# LPCB228_-_POWERUP.net
KiCad netlist of a schematic drawn in Altium Designer
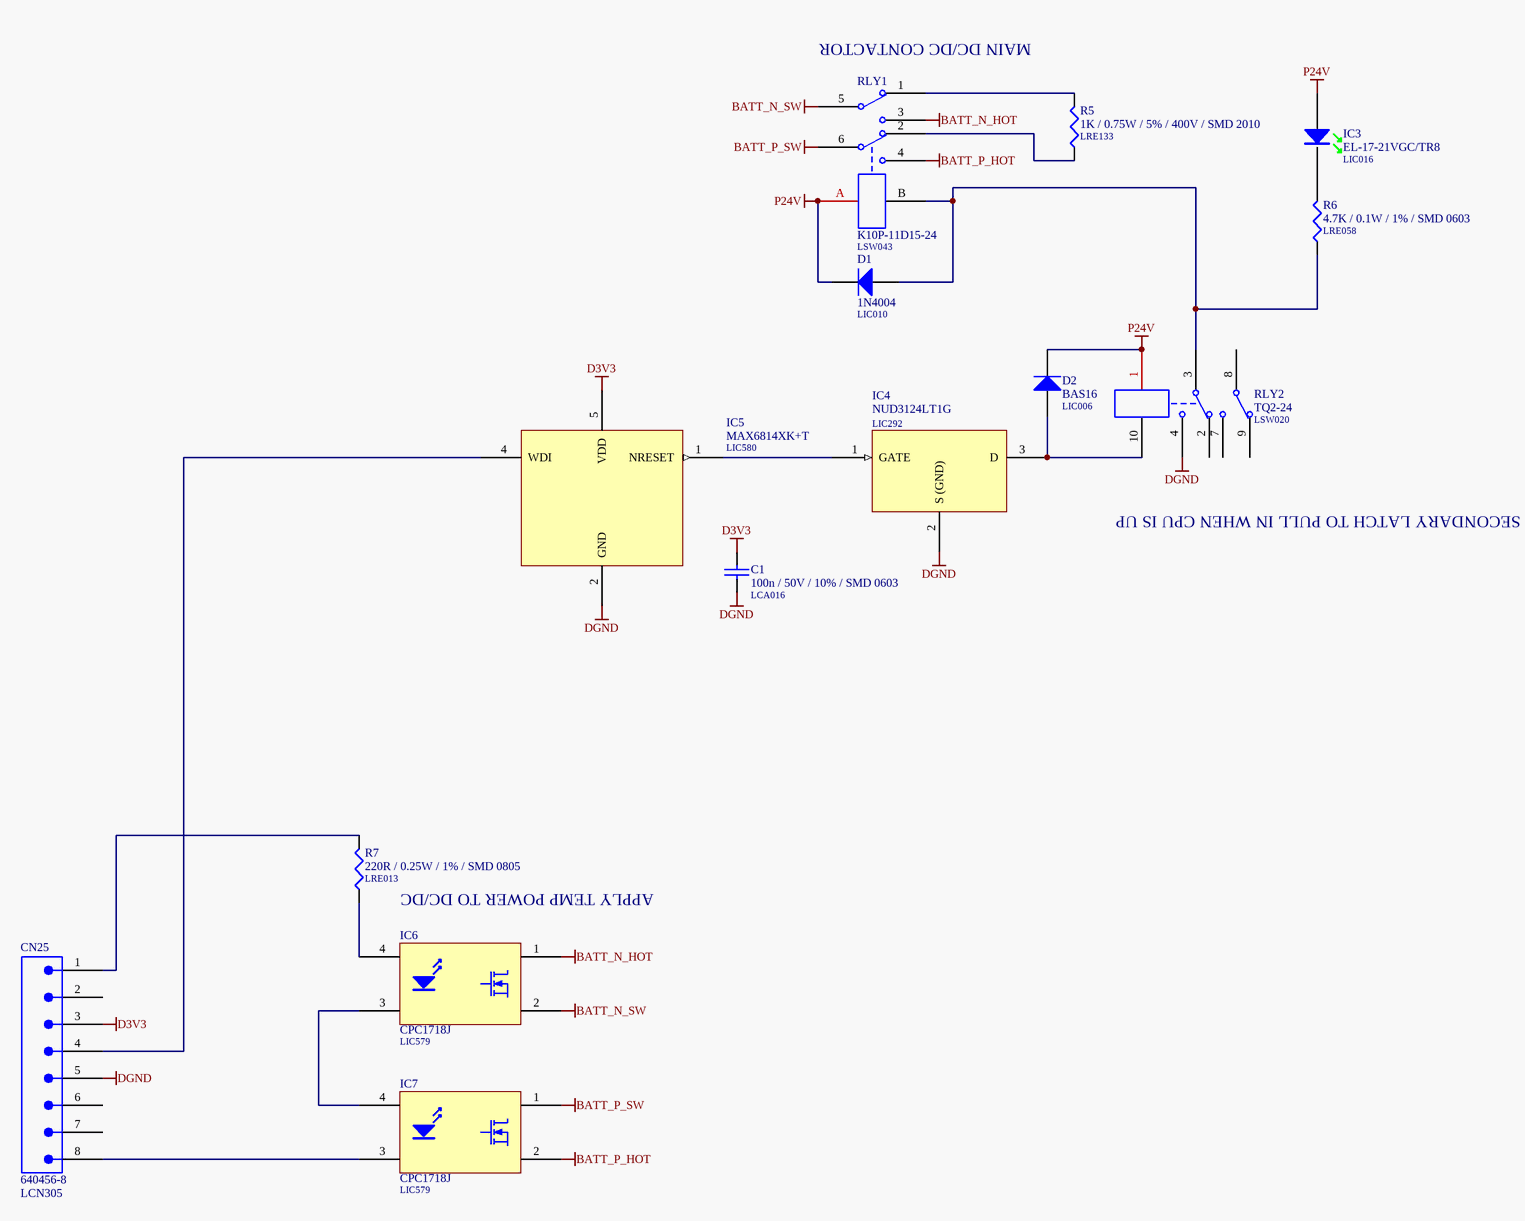
[diagram p0: LPCB228 - POWERUP.SchDoc]

(export (version "E")
  (design (tool "Eeschema 10.0.6"))
  (components
    (comp (ref "C1")
      (value "100n / 50V / 10% / SMD 0603")
      (footprint "LFP011__CC1608-0603-IPC7351_B")
      (description "Capacitor, Ceramic Chip, 100nF (0.1uF), 50V, 5%, SMD 0603 [LCA016]")
      (fields (field (name "LDL_NUMBER") "LCA016"))
      (libsource (lib "LDL_Capacitors") (part "100n / 50V / 10% / SMD 0603"))
    )
    (comp (ref "CN25")
      (value "640456-8")
      (footprint "640456-8")
      (description "Connector, Male Header, 8 Way")
      (fields (field (name "LDL_NUMBER") "LCN305"))
      (libsource (lib "LDL_Connectors") (part "640456-8"))
    )
    (comp (ref "D1")
      (value "1N4004")
      (footprint "DO-41")
      (description "Diode, General Purpose Rectifier, 1A, PTH [LIC010]")
      (fields (field (name "LDL_NUMBER") "LIC010"))
      (libsource (lib "LDL_Semiconductors") (part "1N4004"))
    )
    (comp (ref "D2")
      (value "BAS16")
      (footprint "LFP021__SOT23")
      (description "Diode, Small Signal, 0.2A, 85V, SMD SOT-23 [LIC006]")
      (fields (field (name "LDL_NUMBER") "LIC006"))
      (libsource (lib "LDL_Semiconductors") (part "BAS16"))
    )
    (comp (ref "IC3")
      (value "EL-17-21VGC/TR8")
      (footprint "CR2012-0805-LED")
      (description "LED, SMD, 0805 Green [LIC016]")
      (fields (field (name "LDL_NUMBER") "LIC016"))
      (libsource (lib "LDL_Semiconductors") (part "EL-17-21VGC/TR8"))
    )
    (comp (ref "IC4")
      (value "NUD3124LT1G")
      (footprint "LFP021__SOT23")
      (description "IC, Relay Driver, 28V Industrial, SMD SOT23 [LIC292]")
      (fields (field (name "LDL_NUMBER") "LIC292"))
      (libsource (lib "LDL_Semiconductors") (part "NUD3124LT1G"))
    )
    (comp (ref "IC5")
      (value "MAX6814XK+T")
      (footprint "LFP047__SOT353")
      (description "IC, Watchdog, SMD [LIC580]")
      (fields (field (name "LDL_NUMBER") "LIC580"))
      (libsource (lib "LDL_Semiconductors") (part "MAX6814XK+T"))
    )
    (comp (ref "IC6")
      (value "CPC1718J")
      (footprint "ISOPLUS-264")
      (description "IC, Solid State Relay, PTH [LIC579]")
      (fields (field (name "LDL_NUMBER") "LIC579"))
      (libsource (lib "LDL_Semiconductors") (part "CPC1718J"))
    )
    (comp (ref "IC7")
      (value "CPC1718J")
      (footprint "ISOPLUS-264")
      (description "IC, Solid State Relay, PTH [LIC579]")
      (fields (field (name "LDL_NUMBER") "LIC579"))
      (libsource (lib "LDL_Semiconductors") (part "CPC1718J"))
    )
    (comp (ref "R5")
      (value "1K / 0.75W / 5% / 400V / SMD 2010")
      (footprint "LFP060__CR5025-2010")
      (description "Resistor, Thick Film, 1K, 0.75W, 5%, 400V, SMD 2010 [LRE133]")
      (fields (field (name "LDL_NUMBER") "LRE133"))
      (libsource (lib "LDL_Resistors") (part "1K / 0.75W / 5% / 400V / SMD 2010"))
    )
    (comp (ref "R6")
      (value "4.7K / 0.1W / 1% / SMD 0603")
      (footprint "LFP020__CR1608-0603-IPC7351_B")
      (description "Resistor, Ceramic Chip, 4K7, 0.1W, 1%, SMD 0603 [LRE058]")
      (fields (field (name "LDL_NUMBER") "LRE058"))
      (libsource (lib "LDL_Resistors") (part "4.7K / 0.1W / 1% / SMD 0603"))
    )
    (comp (ref "R7")
      (value "220R / 0.25W / 1% / SMD 0805")
      (footprint "LFP029__CR2012-0805")
      (description "Resistor, Ceramic Chip, 220R, 0.25W, 1%, SMD 0805 [LRE013]")
      (fields (field (name "LDL_NUMBER") "LRE013"))
      (libsource (lib "LDL_Resistors") (part "220R / 0.25W / 1% / SMD 0805"))
    )
    (comp (ref "RLY1")
      (value "K10P-11D15-24")
      (footprint "K10P-11D15-24")
      (description "Relay, DPDT, 24V, Socket Mount")
      (fields (field (name "LDL_NUMBER") "LSW043"))
      (libsource (lib "LDL_Switching") (part "K10P-11D15-24"))
    )
    (comp (ref "RLY2")
      (value "TQ2-24")
      (footprint "TQ2")
      (description "Relay, DPDT, Non Latching, 24VDC Coil, 1A Rating, PTH")
      (fields (field (name "LDL_NUMBER") "LSW020"))
      (libsource (lib "LDL_Switching") (part "TQ2-24"))
    )
  )
  (nets
    (net (code "1") (name "BATT_N_HOT") (class "Default")
      (node (ref "IC6") (pin "1") (pinfunction "1_1") (pintype "passive"))
      (node (ref "RLY1") (pin "3") (pinfunction "3_3") (pintype "passive"))
    )
    (net (code "2") (name "BATT_N_SW") (class "Default")
      (node (ref "IC6") (pin "2") (pinfunction "2_2") (pintype "passive"))
      (node (ref "RLY1") (pin "5") (pinfunction "5_5") (pintype "passive"))
    )
    (net (code "3") (name "BATT_P_HOT") (class "Default")
      (node (ref "IC7") (pin "2") (pinfunction "2_2") (pintype "passive"))
      (node (ref "RLY1") (pin "4") (pinfunction "4_4") (pintype "passive"))
    )
    (net (code "4") (name "BATT_P_SW") (class "Default")
      (node (ref "IC7") (pin "1") (pinfunction "1_1") (pintype "passive"))
      (node (ref "RLY1") (pin "6") (pinfunction "6_6") (pintype "passive"))
    )
    (net (code "5") (name "D3V3") (class "Default")
      (node (ref "C1") (pin "1") (pintype "passive"))
      (node (ref "CN25") (pin "3") (pinfunction "3_3") (pintype "passive"))
      (node (ref "IC5") (pin "5") (pinfunction "VDD_5") (pintype "power_in"))
    )
    (net (code "6") (name "DGND") (class "Default")
      (node (ref "C1") (pin "2") (pintype "passive"))
      (node (ref "CN25") (pin "5") (pinfunction "5_5") (pintype "passive"))
      (node (ref "IC4") (pin "2") (pinfunction "S_(GND)_2") (pintype "passive"))
      (node (ref "IC5") (pin "2") (pinfunction "GND_2") (pintype "power_in"))
      (node (ref "RLY2") (pin "4") (pinfunction "4_4") (pintype "passive"))
    )
    (net (code "7") (name "Net-(CN25-Pad1)") (class "Default")
      (node (ref "CN25") (pin "1") (pinfunction "1_1") (pintype "passive"))
      (node (ref "R7") (pin "2") (pintype "passive"))
    )
    (net (code "8") (name "Net-(CN25-Pad8)") (class "Default")
      (node (ref "CN25") (pin "8") (pinfunction "8_8") (pintype "passive"))
      (node (ref "IC7") (pin "3") (pinfunction "3_3") (pintype "passive"))
    )
    (net (code "9") (name "Net-(D1-PadA)") (class "Default")
      (node (ref "D1") (pin "A") (pinfunction "A_A") (pintype "passive"))
      (node (ref "R6") (pin "1") (pintype "passive"))
      (node (ref "RLY1") (pin "B") (pinfunction "B_B") (pintype "passive"))
      (node (ref "RLY2") (pin "3") (pinfunction "3_3") (pintype "passive"))
    )
    (net (code "10") (name "Net-(D2-A)") (class "Default")
      (node (ref "D2") (pin "1") (pinfunction "A_1") (pintype "passive"))
      (node (ref "IC4") (pin "3") (pinfunction "D_3") (pintype "passive"))
      (node (ref "RLY2") (pin "10") (pinfunction "10_10") (pintype "passive"))
    )
    (net (code "11") (name "Net-(IC3-PadK)") (class "Default")
      (node (ref "IC3") (pin "K") (pintype "passive"))
      (node (ref "R6") (pin "2") (pintype "passive"))
    )
    (net (code "12") (name "Net-(IC4-GATE)") (class "Default")
      (node (ref "IC4") (pin "1") (pinfunction "GATE_1") (pintype "input"))
      (node (ref "IC5") (pin "1") (pinfunction "NRESET_1") (pintype "output"))
    )
    (net (code "13") (name "Net-(IC5-WDI)") (class "Default")
      (node (ref "CN25") (pin "4") (pinfunction "4_4") (pintype "passive"))
      (node (ref "IC5") (pin "4") (pinfunction "WDI_4") (pintype "passive"))
    )
    (net (code "14") (name "Net-(IC6-Pad3)") (class "Default")
      (node (ref "IC6") (pin "3") (pinfunction "3_3") (pintype "passive"))
      (node (ref "IC7") (pin "4") (pinfunction "4_4") (pintype "passive"))
    )
    (net (code "15") (name "Net-(IC6-Pad4)") (class "Default")
      (node (ref "IC6") (pin "4") (pinfunction "4_4") (pintype "passive"))
      (node (ref "R7") (pin "1") (pintype "passive"))
    )
    (net (code "16") (name "Net-(R5-Pad1)") (class "Default")
      (node (ref "R5") (pin "1") (pintype "passive"))
      (node (ref "RLY1") (pin "2") (pinfunction "2_2") (pintype "passive"))
    )
    (net (code "17") (name "Net-(R5-Pad2)") (class "Default")
      (node (ref "R5") (pin "2") (pintype "passive"))
      (node (ref "RLY1") (pin "1") (pinfunction "1_1") (pintype "passive"))
    )
    (net (code "18") (name "P24V") (class "Default")
      (node (ref "D1") (pin "K") (pinfunction "K_K") (pintype "passive"))
      (node (ref "D2") (pin "3") (pinfunction "K_3") (pintype "passive"))
      (node (ref "IC3") (pin "A") (pintype "passive"))
      (node (ref "RLY1") (pin "A") (pinfunction "A_A") (pintype "passive"))
      (node (ref "RLY2") (pin "1") (pinfunction "1_1") (pintype "passive"))
    )
    (net (code "19") (name "unconnected-(CN25-Pad2)") (class "Default")
      (node (ref "CN25") (pin "2") (pinfunction "2_2") (pintype "passive"))
    )
    (net (code "20") (name "unconnected-(CN25-Pad6)") (class "Default")
      (node (ref "CN25") (pin "6") (pinfunction "6_6") (pintype "passive"))
    )
    (net (code "21") (name "unconnected-(CN25-Pad7)") (class "Default")
      (node (ref "CN25") (pin "7") (pinfunction "7_7") (pintype "passive"))
    )
    (net (code "22") (name "unconnected-(RLY2-Pad2)") (class "Default")
      (node (ref "RLY2") (pin "2") (pinfunction "2_2") (pintype "passive"))
    )
    (net (code "23") (name "unconnected-(RLY2-Pad7)") (class "Default")
      (node (ref "RLY2") (pin "7") (pinfunction "7_7") (pintype "passive"))
    )
    (net (code "24") (name "unconnected-(RLY2-Pad8)") (class "Default")
      (node (ref "RLY2") (pin "8") (pinfunction "8_8") (pintype "passive"))
    )
    (net (code "25") (name "unconnected-(RLY2-Pad9)") (class "Default")
      (node (ref "RLY2") (pin "9") (pinfunction "9_9") (pintype "passive"))
    )
  )
)
